# wavtrigger.net
KiCad netlist of a schematic drawn in EAGLE
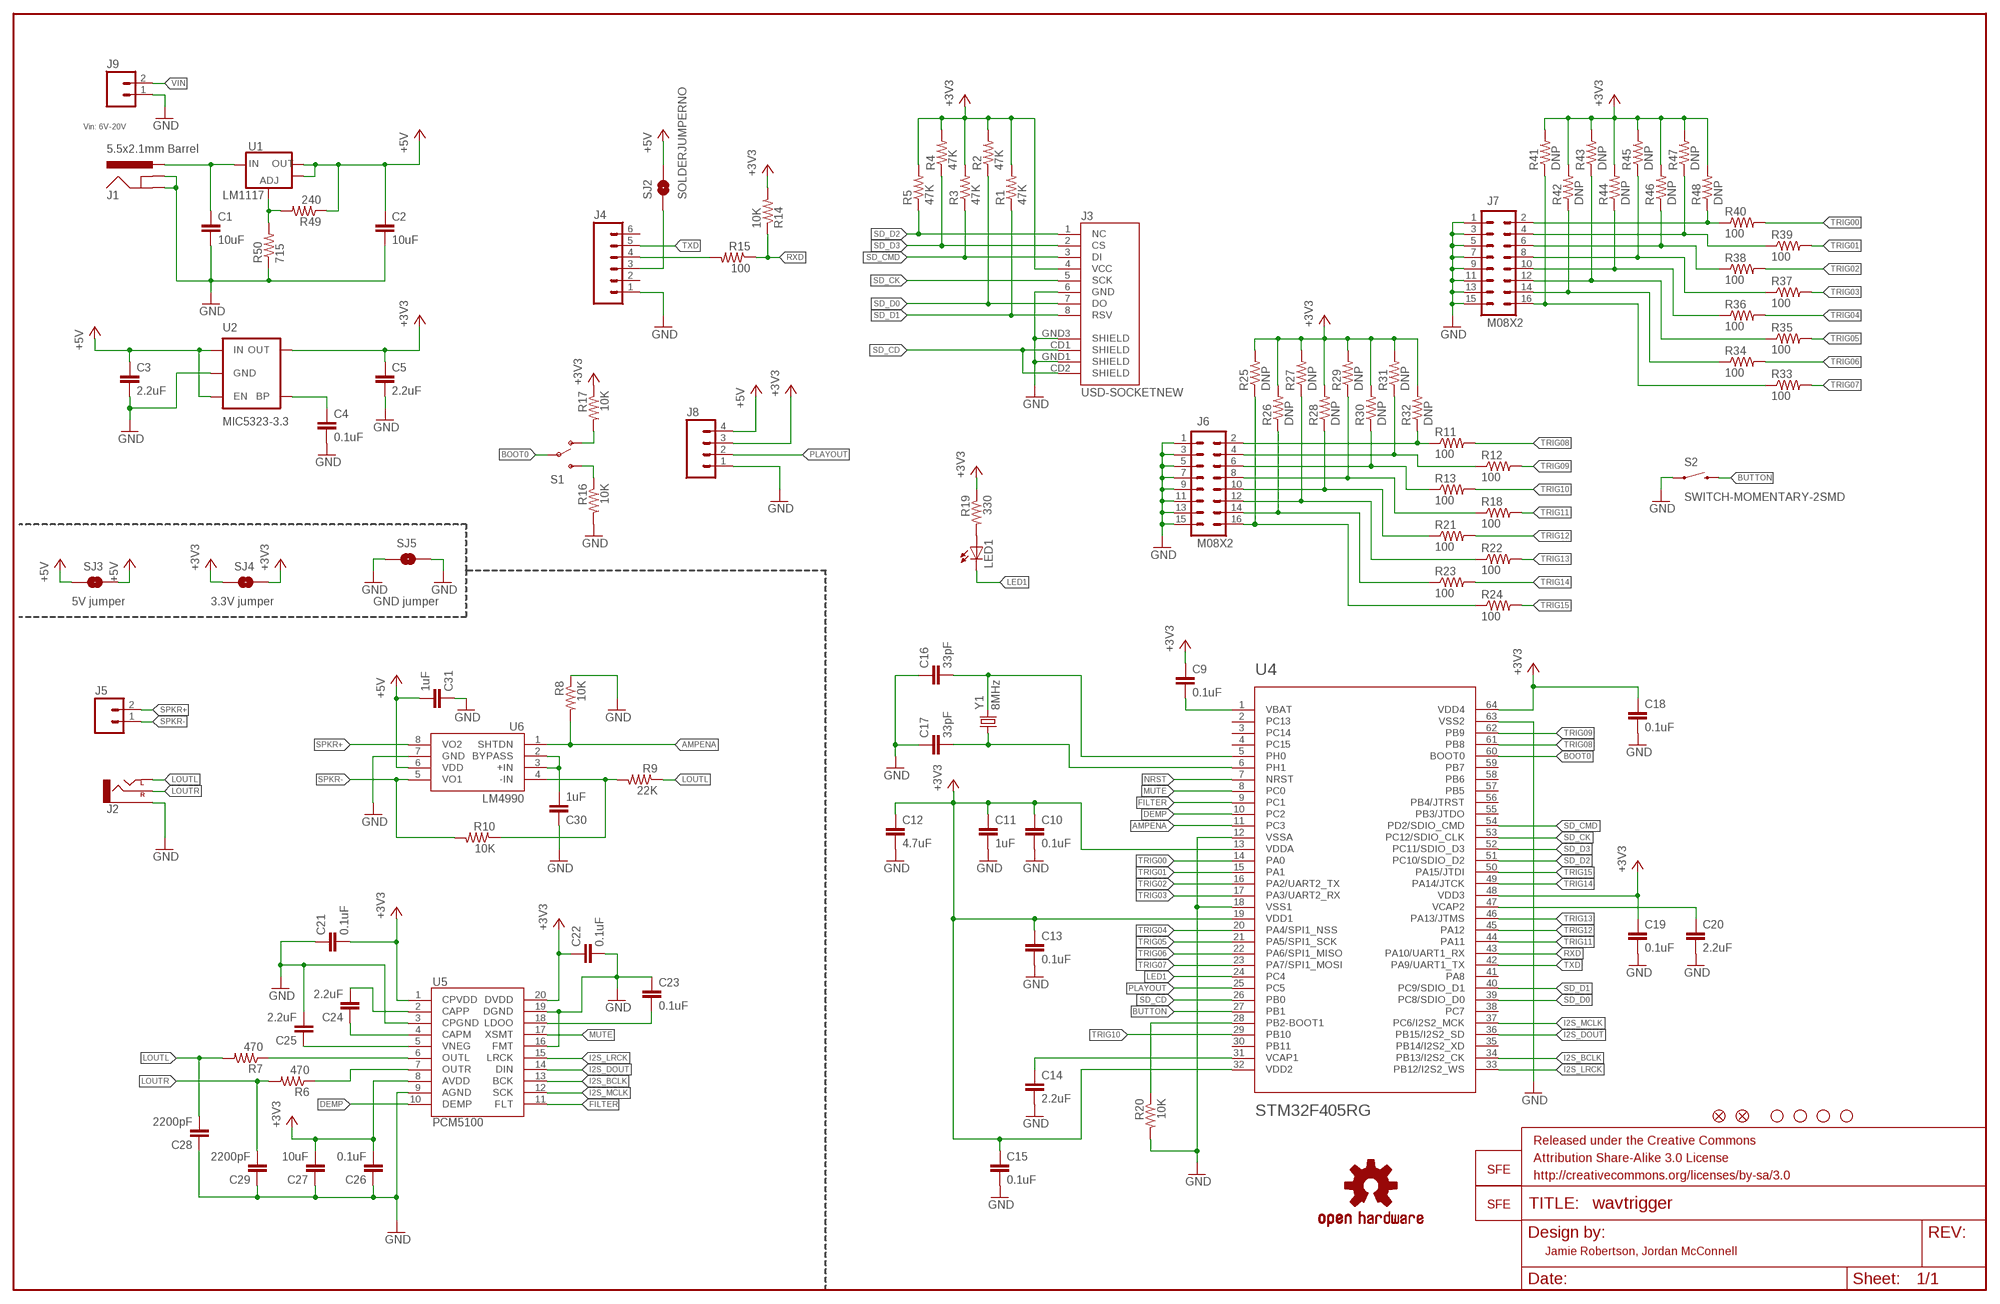
[diagram p0: schematic, sheet 1]

(export (version "E")
  (design (tool "Eeschema 10.0.6"))
  (components
    (comp (ref "C1")
      (value "10uF")
      (footprint "eagle-import:1210")
      (libsource (lib "eagle-import") (part "10UF50V20%(1210)"))
    )
    (comp (ref "C2")
      (value "10uF")
      (footprint "eagle-import:0805")
      (libsource (lib "eagle-import") (part "1UF-25V-10%(0805)"))
    )
    (comp (ref "C3")
      (value "2.2uF")
      (footprint "eagle-import:0805")
      (libsource (lib "eagle-import") (part "1UF-25V-10%(0805)"))
    )
    (comp (ref "C4")
      (value "0.1uF")
      (footprint "eagle-import:0603-CAP")
      (libsource (lib "eagle-import") (part "CAP0603-CAP"))
    )
    (comp (ref "C5")
      (value "2.2uF")
      (footprint "eagle-import:0805")
      (libsource (lib "eagle-import") (part "1UF-25V-10%(0805)"))
    )
    (comp (ref "C9")
      (value "0.1uF")
      (footprint "eagle-import:0603-CAP")
      (libsource (lib "eagle-import") (part "CAP0603-CAP"))
    )
    (comp (ref "C10")
      (value "0.1uF")
      (footprint "eagle-import:0603-CAP")
      (libsource (lib "eagle-import") (part "CAP0603-CAP"))
    )
    (comp (ref "C11")
      (value "1uF")
      (footprint "eagle-import:0603-CAP")
      (libsource (lib "eagle-import") (part "CAP0603-CAP"))
    )
    (comp (ref "C12")
      (value "4.7uF")
      (footprint "eagle-import:0603-CAP")
      (libsource (lib "eagle-import") (part "CAP0603-CAP"))
    )
    (comp (ref "C13")
      (value "0.1uF")
      (footprint "eagle-import:0603-CAP")
      (libsource (lib "eagle-import") (part "CAP0603-CAP"))
    )
    (comp (ref "C14")
      (value "2.2uF")
      (footprint "eagle-import:0603-CAP")
      (libsource (lib "eagle-import") (part "CAP0603-CAP"))
    )
    (comp (ref "C15")
      (value "0.1uF")
      (footprint "eagle-import:0603-CAP")
      (libsource (lib "eagle-import") (part "CAP0603-CAP"))
    )
    (comp (ref "C16")
      (value "33pF")
      (footprint "eagle-import:0603-CAP")
      (libsource (lib "eagle-import") (part "CAP0603-CAP"))
    )
    (comp (ref "C17")
      (value "33pF")
      (footprint "eagle-import:0603-CAP")
      (libsource (lib "eagle-import") (part "CAP0603-CAP"))
    )
    (comp (ref "C18")
      (value "0.1uF")
      (footprint "eagle-import:0603-CAP")
      (libsource (lib "eagle-import") (part "CAP0603-CAP"))
    )
    (comp (ref "C19")
      (value "0.1uF")
      (footprint "eagle-import:0603-CAP")
      (libsource (lib "eagle-import") (part "CAP0603-CAP"))
    )
    (comp (ref "C20")
      (value "2.2uF")
      (footprint "eagle-import:0603-CAP")
      (libsource (lib "eagle-import") (part "CAP0603-CAP"))
    )
    (comp (ref "C21")
      (value "0.1uF")
      (footprint "eagle-import:0603-CAP")
      (libsource (lib "eagle-import") (part "CAP0603-CAP"))
    )
    (comp (ref "C22")
      (value "0.1uF")
      (footprint "eagle-import:0603-CAP")
      (libsource (lib "eagle-import") (part "CAP0603-CAP"))
    )
    (comp (ref "C23")
      (value "0.1uF")
      (footprint "eagle-import:0603-CAP")
      (libsource (lib "eagle-import") (part "CAP0603-CAP"))
    )
    (comp (ref "C24")
      (value "2.2uF")
      (footprint "eagle-import:0603-CAP")
      (libsource (lib "eagle-import") (part "CAP0603-CAP"))
    )
    (comp (ref "C25")
      (value "2.2uF")
      (footprint "eagle-import:0603-CAP")
      (libsource (lib "eagle-import") (part "CAP0603-CAP"))
    )
    (comp (ref "C26")
      (value "0.1uF")
      (footprint "eagle-import:0603-CAP")
      (libsource (lib "eagle-import") (part "CAP0603-CAP"))
    )
    (comp (ref "C27")
      (value "10uF")
      (footprint "eagle-import:0603-CAP")
      (libsource (lib "eagle-import") (part "CAP0603-CAP"))
    )
    (comp (ref "C28")
      (value "2200pF")
      (footprint "eagle-import:0603-CAP")
      (libsource (lib "eagle-import") (part "CAP0603-CAP"))
    )
    (comp (ref "C29")
      (value "2200pF")
      (footprint "eagle-import:0603-CAP")
      (libsource (lib "eagle-import") (part "CAP0603-CAP"))
    )
    (comp (ref "C30")
      (value "1uF")
      (footprint "eagle-import:0603-CAP")
      (libsource (lib "eagle-import") (part "CAP0603-CAP"))
    )
    (comp (ref "C31")
      (value "1uF")
      (footprint "eagle-import:0603-CAP")
      (libsource (lib "eagle-import") (part "CAP0603-CAP"))
    )
    (comp (ref "FID1")
      (value "FIDUCIAL1X2")
      (footprint "eagle-import:FIDUCIAL-1X2")
      (libsource (lib "eagle-import") (part "FIDUCIAL1X2"))
    )
    (comp (ref "FID2")
      (value "FIDUCIAL1X2")
      (footprint "eagle-import:FIDUCIAL-1X2")
      (libsource (lib "eagle-import") (part "FIDUCIAL1X2"))
    )
    (comp (ref "FRAME2")
      (value "FRAME-LEDGER")
      (footprint "eagle-import:CREATIVE_COMMONS")
      (libsource (lib "eagle-import") (part "FRAME-LEDGER"))
    )
    (comp (ref "J1")
      (value "5.5x2.1mm Barrel")
      (footprint "eagle-import:POWER_JACK_SMD")
      (libsource (lib "eagle-import") (part "POWER_JACKSMD"))
    )
    (comp (ref "J2")
      (value "AUDIO-JACKSMD2")
      (footprint "eagle-import:AUDIO-JACK-3.5MM-SMD")
      (libsource (lib "eagle-import") (part "AUDIO-JACKSMD2"))
    )
    (comp (ref "J3")
      (value "USD-SOCKETNEW")
      (footprint "eagle-import:MICRO-SD-SOCKET-PP")
      (libsource (lib "eagle-import") (part "USD-SOCKETNEW"))
    )
    (comp (ref "J4")
      (value "M06SIP")
      (footprint "eagle-import:1X06")
      (libsource (lib "eagle-import") (part "M06SIP"))
    )
    (comp (ref "J5")
      (value "M02PTH")
      (footprint "eagle-import:1X02")
      (libsource (lib "eagle-import") (part "M02PTH"))
    )
    (comp (ref "J6")
      (value "M08X2")
      (footprint "eagle-import:2X8")
      (libsource (lib "eagle-import") (part "M08X2"))
    )
    (comp (ref "J7")
      (value "M08X2")
      (footprint "eagle-import:2X8")
      (libsource (lib "eagle-import") (part "M08X2"))
    )
    (comp (ref "J8")
      (value "M04PTH")
      (footprint "eagle-import:1X04")
      (libsource (lib "eagle-import") (part "M04PTH"))
    )
    (comp (ref "J9")
      (value "M02PTH")
      (footprint "eagle-import:1X02")
      (libsource (lib "eagle-import") (part "M02PTH"))
    )
    (comp (ref "LED1")
      (value "LED0603")
      (footprint "eagle-import:LED-0603")
      (libsource (lib "eagle-import") (part "LED0603"))
    )
    (comp (ref "LOGO1")
      (value "OSHW-LOGOL")
      (footprint "eagle-import:OSHW-LOGO-L")
      (libsource (lib "eagle-import") (part "OSHW-LOGOL"))
    )
    (comp (ref "LOGO2")
      (value "LOGO-SFENEW")
      (footprint "eagle-import:SFE-NEW-WEBLOGO")
      (libsource (lib "eagle-import") (part "LOGO-SFENEW"))
    )
    (comp (ref "LOGO3")
      (value "LOGO-SFESK")
      (footprint "eagle-import:SFE-LOGO-FLAME")
      (libsource (lib "eagle-import") (part "LOGO-SFESK"))
    )
    (comp (ref "R1")
      (value "47K")
      (footprint "eagle-import:0603-RES")
      (libsource (lib "eagle-import") (part "RESISTOR0603-RES"))
    )
    (comp (ref "R2")
      (value "47K")
      (footprint "eagle-import:0603-RES")
      (libsource (lib "eagle-import") (part "RESISTOR0603-RES"))
    )
    (comp (ref "R3")
      (value "47K")
      (footprint "eagle-import:0603-RES")
      (libsource (lib "eagle-import") (part "RESISTOR0603-RES"))
    )
    (comp (ref "R4")
      (value "47K")
      (footprint "eagle-import:0603-RES")
      (libsource (lib "eagle-import") (part "RESISTOR0603-RES"))
    )
    (comp (ref "R5")
      (value "47K")
      (footprint "eagle-import:0603-RES")
      (libsource (lib "eagle-import") (part "RESISTOR0603-RES"))
    )
    (comp (ref "R6")
      (value "470")
      (footprint "eagle-import:0603-RES")
      (libsource (lib "eagle-import") (part "RESISTOR0603-RES"))
    )
    (comp (ref "R7")
      (value "470")
      (footprint "eagle-import:0603-RES")
      (libsource (lib "eagle-import") (part "RESISTOR0603-RES"))
    )
    (comp (ref "R8")
      (value "10K")
      (footprint "eagle-import:0603-RES")
      (libsource (lib "eagle-import") (part "RESISTOR0603-RES"))
    )
    (comp (ref "R9")
      (value "22K")
      (footprint "eagle-import:0603-RES")
      (libsource (lib "eagle-import") (part "RESISTOR0603-RES"))
    )
    (comp (ref "R10")
      (value "10K")
      (footprint "eagle-import:0603-RES")
      (libsource (lib "eagle-import") (part "RESISTOR0603-RES"))
    )
    (comp (ref "R11")
      (value "100")
      (footprint "eagle-import:0603-RES")
      (libsource (lib "eagle-import") (part "RESISTOR0603-RES"))
    )
    (comp (ref "R12")
      (value "100")
      (footprint "eagle-import:0603-RES")
      (libsource (lib "eagle-import") (part "RESISTOR0603-RES"))
    )
    (comp (ref "R13")
      (value "100")
      (footprint "eagle-import:0603-RES")
      (libsource (lib "eagle-import") (part "RESISTOR0603-RES"))
    )
    (comp (ref "R14")
      (value "10K")
      (footprint "eagle-import:0603-RES")
      (libsource (lib "eagle-import") (part "RESISTOR0603-RES"))
    )
    (comp (ref "R15")
      (value "100")
      (footprint "eagle-import:0603-RES")
      (libsource (lib "eagle-import") (part "RESISTOR0603-RES"))
    )
    (comp (ref "R16")
      (value "10K")
      (footprint "eagle-import:0603-RES")
      (libsource (lib "eagle-import") (part "RESISTOR0603-RES"))
    )
    (comp (ref "R17")
      (value "10K")
      (footprint "eagle-import:0603-RES")
      (libsource (lib "eagle-import") (part "RESISTOR0603-RES"))
    )
    (comp (ref "R18")
      (value "100")
      (footprint "eagle-import:0603-RES")
      (libsource (lib "eagle-import") (part "RESISTOR0603-RES"))
    )
    (comp (ref "R19")
      (value "330")
      (footprint "eagle-import:0603-RES")
      (libsource (lib "eagle-import") (part "RESISTOR0603-RES"))
    )
    (comp (ref "R20")
      (value "10K")
      (footprint "eagle-import:0603-RES")
      (libsource (lib "eagle-import") (part "RESISTOR0603-RES"))
    )
    (comp (ref "R21")
      (value "100")
      (footprint "eagle-import:0603-RES")
      (libsource (lib "eagle-import") (part "RESISTOR0603-RES"))
    )
    (comp (ref "R22")
      (value "100")
      (footprint "eagle-import:0603-RES")
      (libsource (lib "eagle-import") (part "RESISTOR0603-RES"))
    )
    (comp (ref "R23")
      (value "100")
      (footprint "eagle-import:0603-RES")
      (libsource (lib "eagle-import") (part "RESISTOR0603-RES"))
    )
    (comp (ref "R24")
      (value "100")
      (footprint "eagle-import:0603-RES")
      (libsource (lib "eagle-import") (part "RESISTOR0603-RES"))
    )
    (comp (ref "R25")
      (value "DNP")
      (footprint "eagle-import:0603-RES")
      (libsource (lib "eagle-import") (part "RESISTOR0603-RES"))
    )
    (comp (ref "R26")
      (value "DNP")
      (footprint "eagle-import:0603-RES")
      (libsource (lib "eagle-import") (part "RESISTOR0603-RES"))
    )
    (comp (ref "R27")
      (value "DNP")
      (footprint "eagle-import:0603-RES")
      (libsource (lib "eagle-import") (part "RESISTOR0603-RES"))
    )
    (comp (ref "R28")
      (value "DNP")
      (footprint "eagle-import:0603-RES")
      (libsource (lib "eagle-import") (part "RESISTOR0603-RES"))
    )
    (comp (ref "R29")
      (value "DNP")
      (footprint "eagle-import:0603-RES")
      (libsource (lib "eagle-import") (part "RESISTOR0603-RES"))
    )
    (comp (ref "R30")
      (value "DNP")
      (footprint "eagle-import:0603-RES")
      (libsource (lib "eagle-import") (part "RESISTOR0603-RES"))
    )
    (comp (ref "R31")
      (value "DNP")
      (footprint "eagle-import:0603-RES")
      (libsource (lib "eagle-import") (part "RESISTOR0603-RES"))
    )
    (comp (ref "R32")
      (value "DNP")
      (footprint "eagle-import:0603-RES")
      (libsource (lib "eagle-import") (part "RESISTOR0603-RES"))
    )
    (comp (ref "R33")
      (value "100")
      (footprint "eagle-import:0603-RES")
      (libsource (lib "eagle-import") (part "RESISTOR0603-RES"))
    )
    (comp (ref "R34")
      (value "100")
      (footprint "eagle-import:0603-RES")
      (libsource (lib "eagle-import") (part "RESISTOR0603-RES"))
    )
    (comp (ref "R35")
      (value "100")
      (footprint "eagle-import:0603-RES")
      (libsource (lib "eagle-import") (part "RESISTOR0603-RES"))
    )
    (comp (ref "R36")
      (value "100")
      (footprint "eagle-import:0603-RES")
      (libsource (lib "eagle-import") (part "RESISTOR0603-RES"))
    )
    (comp (ref "R37")
      (value "100")
      (footprint "eagle-import:0603-RES")
      (libsource (lib "eagle-import") (part "RESISTOR0603-RES"))
    )
    (comp (ref "R38")
      (value "100")
      (footprint "eagle-import:0603-RES")
      (libsource (lib "eagle-import") (part "RESISTOR0603-RES"))
    )
    (comp (ref "R39")
      (value "100")
      (footprint "eagle-import:0603-RES")
      (libsource (lib "eagle-import") (part "RESISTOR0603-RES"))
    )
    (comp (ref "R40")
      (value "100")
      (footprint "eagle-import:0603-RES")
      (libsource (lib "eagle-import") (part "RESISTOR0603-RES"))
    )
    (comp (ref "R41")
      (value "DNP")
      (footprint "eagle-import:0603-RES")
      (libsource (lib "eagle-import") (part "RESISTOR0603-RES"))
    )
    (comp (ref "R42")
      (value "DNP")
      (footprint "eagle-import:0603-RES")
      (libsource (lib "eagle-import") (part "RESISTOR0603-RES"))
    )
    (comp (ref "R43")
      (value "DNP")
      (footprint "eagle-import:0603-RES")
      (libsource (lib "eagle-import") (part "RESISTOR0603-RES"))
    )
    (comp (ref "R44")
      (value "DNP")
      (footprint "eagle-import:0603-RES")
      (libsource (lib "eagle-import") (part "RESISTOR0603-RES"))
    )
    (comp (ref "R45")
      (value "DNP")
      (footprint "eagle-import:0603-RES")
      (libsource (lib "eagle-import") (part "RESISTOR0603-RES"))
    )
    (comp (ref "R46")
      (value "DNP")
      (footprint "eagle-import:0603-RES")
      (libsource (lib "eagle-import") (part "RESISTOR0603-RES"))
    )
    (comp (ref "R47")
      (value "DNP")
      (footprint "eagle-import:0603-RES")
      (libsource (lib "eagle-import") (part "RESISTOR0603-RES"))
    )
    (comp (ref "R48")
      (value "DNP")
      (footprint "eagle-import:0603-RES")
      (libsource (lib "eagle-import") (part "RESISTOR0603-RES"))
    )
    (comp (ref "R49")
      (value "240")
      (footprint "eagle-import:0603-RES")
      (libsource (lib "eagle-import") (part "240OHM1/10W1%(0603)"))
    )
    (comp (ref "R50")
      (value "715")
      (footprint "eagle-import:0603-RES")
      (libsource (lib "eagle-import") (part "RESISTOR0603"))
    )
    (comp (ref "S1")
      (value "SWITCH-SPDT-SMD-A")
      (footprint "eagle-import:SWITCH-SPST-SMD-A")
      (libsource (lib "eagle-import") (part "SWITCH-SPDT-SMD-A"))
    )
    (comp (ref "S2")
      (value "SWITCH-MOMENTARY-2SMD")
      (footprint "eagle-import:TACTILE_SWITCH_SMD")
      (libsource (lib "eagle-import") (part "SWITCH-MOMENTARY-2SMD"))
    )
    (comp (ref "SJ2")
      (value "SOLDERJUMPERNO")
      (footprint "eagle-import:SJ_2S-NO")
      (libsource (lib "eagle-import") (part "SOLDERJUMPERNO"))
    )
    (comp (ref "SJ3")
      (value "SOLDERJUMPERTRACE")
      (footprint "eagle-import:SJ_2S-TRACE")
      (libsource (lib "eagle-import") (part "SOLDERJUMPERTRACE"))
    )
    (comp (ref "SJ4")
      (value "SOLDERJUMPERTRACE")
      (footprint "eagle-import:SJ_2S-TRACE")
      (libsource (lib "eagle-import") (part "SOLDERJUMPERTRACE"))
    )
    (comp (ref "SJ5")
      (value "SOLDERJUMPERTRACE")
      (footprint "eagle-import:SJ_2S-TRACE")
      (libsource (lib "eagle-import") (part "SOLDERJUMPERTRACE"))
    )
    (comp (ref "STANDOFF1")
      (value "STAND-OFF")
      (footprint "eagle-import:STAND-OFF")
      (libsource (lib "eagle-import") (part "STAND-OFF"))
    )
    (comp (ref "STANDOFF2")
      (value "STAND-OFF")
      (footprint "eagle-import:STAND-OFF")
      (libsource (lib "eagle-import") (part "STAND-OFF"))
    )
    (comp (ref "STANDOFF3")
      (value "STAND-OFF")
      (footprint "eagle-import:STAND-OFF")
      (libsource (lib "eagle-import") (part "STAND-OFF"))
    )
    (comp (ref "STANDOFF4")
      (value "STAND-OFF")
      (footprint "eagle-import:STAND-OFF")
      (libsource (lib "eagle-import") (part "STAND-OFF"))
    )
    (comp (ref "U1")
      (value "V_REG_LM1117SOT223")
      (footprint "eagle-import:SOT223")
      (libsource (lib "eagle-import") (part "V_REG_LM1117SOT223"))
    )
    (comp (ref "U2")
      (value "MIC5323-3.3")
      (footprint "eagle-import:SOT23-5")
      (libsource (lib "eagle-import") (part "MIC52053.3V"))
    )
    (comp (ref "U4")
      (value "STM32F405RG")
      (footprint "eagle-import:TQFP64")
      (libsource (lib "eagle-import") (part "STM32F405RG"))
    )
    (comp (ref "U5")
      (value "PCM5100")
      (footprint "eagle-import:PW_R-PDSO-G20")
      (libsource (lib "eagle-import") (part "PCM5100"))
    )
    (comp (ref "U6")
      (value "LM4990")
      (footprint "eagle-import:S-PDSO-G08")
      (libsource (lib "eagle-import") (part "LM4990"))
    )
    (comp (ref "Y1")
      (value "8MHz")
      (footprint "eagle-import:HC49UP")
      (libsource (lib "eagle-import") (part "CRYSTALSMD"))
    )
  )
  (nets
    (net (code "1") (name "+3V3") (class "Default")
      (node (ref "C10") (pin "1") (pinfunction "1_1") (pintype "passive"))
      (node (ref "C11") (pin "1") (pinfunction "1_1") (pintype "passive"))
      (node (ref "C12") (pin "1") (pinfunction "1_1") (pintype "passive"))
      (node (ref "C13") (pin "1") (pinfunction "1_1") (pintype "passive"))
      (node (ref "C15") (pin "1") (pinfunction "1_1") (pintype "passive"))
      (node (ref "C18") (pin "1") (pinfunction "1_1") (pintype "passive"))
      (node (ref "C19") (pin "1") (pinfunction "1_1") (pintype "passive"))
      (node (ref "C21") (pin "2") (pinfunction "2_2") (pintype "passive"))
      (node (ref "C22") (pin "1") (pinfunction "1_1") (pintype "passive"))
      (node (ref "C26") (pin "2") (pinfunction "2_2") (pintype "passive"))
      (node (ref "C27") (pin "2") (pinfunction "2_2") (pintype "passive"))
      (node (ref "C5") (pin "1") (pinfunction "1_1") (pintype "passive"))
      (node (ref "C9") (pin "1") (pinfunction "1_1") (pintype "passive"))
      (node (ref "J3") (pin "4") (pinfunction "VCC_4") (pintype "bidirectional"))
      (node (ref "J8") (pin "3") (pinfunction "3_3") (pintype "passive"))
      (node (ref "R1") (pin "2") (pinfunction "2_2") (pintype "passive"))
      (node (ref "R14") (pin "2") (pinfunction "2_2") (pintype "passive"))
      (node (ref "R17") (pin "1") (pinfunction "1_1") (pintype "passive"))
      (node (ref "R19") (pin "1") (pinfunction "1_1") (pintype "passive"))
      (node (ref "R2") (pin "2") (pinfunction "2_2") (pintype "passive"))
      (node (ref "R25") (pin "2") (pinfunction "2_2") (pintype "passive"))
      (node (ref "R26") (pin "2") (pinfunction "2_2") (pintype "passive"))
      (node (ref "R27") (pin "2") (pinfunction "2_2") (pintype "passive"))
      (node (ref "R28") (pin "2") (pinfunction "2_2") (pintype "passive"))
      (node (ref "R29") (pin "2") (pinfunction "2_2") (pintype "passive"))
      (node (ref "R3") (pin "2") (pinfunction "2_2") (pintype "passive"))
      (node (ref "R30") (pin "2") (pinfunction "2_2") (pintype "passive"))
      (node (ref "R31") (pin "2") (pinfunction "2_2") (pintype "passive"))
      (node (ref "R32") (pin "2") (pinfunction "2_2") (pintype "passive"))
      (node (ref "R4") (pin "2") (pinfunction "2_2") (pintype "passive"))
      (node (ref "R41") (pin "2") (pinfunction "2_2") (pintype "passive"))
      (node (ref "R42") (pin "2") (pinfunction "2_2") (pintype "passive"))
      (node (ref "R43") (pin "2") (pinfunction "2_2") (pintype "passive"))
      (node (ref "R44") (pin "2") (pinfunction "2_2") (pintype "passive"))
      (node (ref "R45") (pin "2") (pinfunction "2_2") (pintype "passive"))
      (node (ref "R46") (pin "2") (pinfunction "2_2") (pintype "passive"))
      (node (ref "R47") (pin "2") (pinfunction "2_2") (pintype "passive"))
      (node (ref "R48") (pin "2") (pinfunction "2_2") (pintype "passive"))
      (node (ref "R5") (pin "2") (pinfunction "2_2") (pintype "passive"))
      (node (ref "SJ4") (pin "1") (pinfunction "1_1") (pintype "passive"))
      (node (ref "SJ4") (pin "2") (pinfunction "2_2") (pintype "passive"))
      (node (ref "U2") (pin "5") (pinfunction "OUT_5") (pintype "passive"))
      (node (ref "U4") (pin "13") (pinfunction "VDDA_13") (pintype "bidirectional"))
      (node (ref "U4") (pin "19") (pinfunction "VDD1_19") (pintype "bidirectional"))
      (node (ref "U4") (pin "32") (pinfunction "VDD2_32") (pintype "bidirectional"))
      (node (ref "U4") (pin "48") (pinfunction "VDD3_48") (pintype "bidirectional"))
      (node (ref "U4") (pin "64") (pinfunction "VDD4_64") (pintype "bidirectional"))
      (node (ref "U5") (pin "1") (pinfunction "CPVDD_1") (pintype "bidirectional"))
      (node (ref "U5") (pin "20") (pinfunction "DVDD_20") (pintype "bidirectional"))
      (node (ref "U5") (pin "8") (pinfunction "AVDD_8") (pintype "bidirectional"))
    )
    (net (code "2") (name "+5V") (class "Default")
      (node (ref "C2") (pin "1") (pinfunction "1_1") (pintype "passive"))
      (node (ref "C3") (pin "1") (pinfunction "1_1") (pintype "passive"))
      (node (ref "C31") (pin "2") (pinfunction "2_2") (pintype "passive"))
      (node (ref "J8") (pin "4") (pinfunction "4_4") (pintype "passive"))
      (node (ref "R49") (pin "1") (pinfunction "1_1") (pintype "passive"))
      (node (ref "SJ2") (pin "2") (pinfunction "2_2") (pintype "passive"))
      (node (ref "SJ3") (pin "1") (pinfunction "1_1") (pintype "passive"))
      (node (ref "SJ3") (pin "2") (pinfunction "2_2") (pintype "passive"))
      (node (ref "U1") (pin "2") (pinfunction "OUT_2") (pintype "output"))
      (node (ref "U1") (pin "4") (pinfunction "OUT_4") (pintype "output"))
      (node (ref "U2") (pin "1") (pinfunction "IN_1") (pintype "input"))
      (node (ref "U2") (pin "3") (pinfunction "EN_3") (pintype "input"))
      (node (ref "U6") (pin "6") (pinfunction "VDD_6") (pintype "bidirectional"))
    )
    (net (code "3") (name "AMPENA") (class "Default")
      (node (ref "R8") (pin "2") (pinfunction "2_2") (pintype "passive"))
      (node (ref "U4") (pin "11") (pinfunction "PC3_11") (pintype "bidirectional"))
      (node (ref "U6") (pin "1") (pinfunction "SHTDN_1") (pintype "bidirectional"))
    )
    (net (code "4") (name "BOOT0") (class "Default")
      (node (ref "S1") (pin "2") (pinfunction "P_2") (pintype "passive"))
      (node (ref "U4") (pin "60") (pinfunction "BOOT0_60") (pintype "bidirectional"))
    )
    (net (code "5") (name "BUTTON") (class "Default")
      (node (ref "S2") (pin "3") (pinfunction "2_3") (pintype "passive"))
      (node (ref "U4") (pin "27") (pinfunction "PB1_27") (pintype "bidirectional"))
    )
    (net (code "6") (name "DEMP") (class "Default")
      (node (ref "U4") (pin "10") (pinfunction "PC2_10") (pintype "bidirectional"))
      (node (ref "U5") (pin "10") (pinfunction "DEMP_10") (pintype "bidirectional"))
    )
    (net (code "7") (name "FILTER") (class "Default")
      (node (ref "U4") (pin "9") (pinfunction "PC1_9") (pintype "bidirectional"))
      (node (ref "U5") (pin "11") (pinfunction "FLT_11") (pintype "bidirectional"))
    )
    (net (code "8") (name "GND") (class "Default")
      (node (ref "C1") (pin "2") (pinfunction "2_2") (pintype "passive"))
      (node (ref "C10") (pin "2") (pinfunction "2_2") (pintype "passive"))
      (node (ref "C11") (pin "2") (pinfunction "2_2") (pintype "passive"))
      (node (ref "C12") (pin "2") (pinfunction "2_2") (pintype "passive"))
      (node (ref "C13") (pin "2") (pinfunction "2_2") (pintype "passive"))
      (node (ref "C14") (pin "2") (pinfunction "2_2") (pintype "passive"))
      (node (ref "C15") (pin "2") (pinfunction "2_2") (pintype "passive"))
      (node (ref "C16") (pin "1") (pinfunction "1_1") (pintype "passive"))
      (node (ref "C17") (pin "1") (pinfunction "1_1") (pintype "passive"))
      (node (ref "C18") (pin "2") (pinfunction "2_2") (pintype "passive"))
      (node (ref "C19") (pin "2") (pinfunction "2_2") (pintype "passive"))
      (node (ref "C2") (pin "2") (pinfunction "2_2") (pintype "passive"))
      (node (ref "C20") (pin "2") (pinfunction "2_2") (pintype "passive"))
      (node (ref "C21") (pin "1") (pinfunction "1_1") (pintype "passive"))
      (node (ref "C22") (pin "2") (pinfunction "2_2") (pintype "passive"))
      (node (ref "C23") (pin "1") (pinfunction "1_1") (pintype "passive"))
      (node (ref "C25") (pin "2") (pinfunction "2_2") (pintype "passive"))
      (node (ref "C26") (pin "1") (pinfunction "1_1") (pintype "passive"))
      (node (ref "C27") (pin "1") (pinfunction "1_1") (pintype "passive"))
      (node (ref "C28") (pin "1") (pinfunction "1_1") (pintype "passive"))
      (node (ref "C29") (pin "1") (pinfunction "1_1") (pintype "passive"))
      (node (ref "C3") (pin "2") (pinfunction "2_2") (pintype "passive"))
      (node (ref "C30") (pin "1") (pinfunction "1_1") (pintype "passive"))
      (node (ref "C31") (pin "1") (pinfunction "1_1") (pintype "passive"))
      (node (ref "C4") (pin "2") (pinfunction "2_2") (pintype "passive"))
      (node (ref "C5") (pin "2") (pinfunction "2_2") (pintype "passive"))
      (node (ref "J1") (pin "GND") (pinfunction "GNDBREAK_GND") (pintype "bidirectional"))
      (node (ref "J1") (pin "P$4") (pinfunction "GND_P$4") (pintype "bidirectional"))
      (node (ref "J2") (pin "SLEEVE") (pinfunction "SLEEVE_SLEEVE") (pintype "bidirectional"))
      (node (ref "J3") (pin "6") (pinfunction "GND_6") (pintype "bidirectional"))
      (node (ref "J3") (pin "GND1") (pinfunction "SHIELD_GND1") (pintype "bidirectional"))
      (node (ref "J3") (pin "GND3") (pinfunction "SHIELD_GND3") (pintype "bidirectional"))
      (node (ref "J4") (pin "1") (pinfunction "1_1") (pintype "passive"))
      (node (ref "J6") (pin "1") (pinfunction "1_1") (pintype "passive"))
      (node (ref "J6") (pin "11") (pinfunction "11_11") (pintype "passive"))
      (node (ref "J6") (pin "13") (pinfunction "13_13") (pintype "passive"))
      (node (ref "J6") (pin "15") (pinfunction "15_15") (pintype "passive"))
      (node (ref "J6") (pin "3") (pinfunction "3_3") (pintype "passive"))
      (node (ref "J6") (pin "5") (pinfunction "5_5") (pintype "passive"))
      (node (ref "J6") (pin "7") (pinfunction "7_7") (pintype "passive"))
      (node (ref "J6") (pin "9") (pinfunction "9_9") (pintype "passive"))
      (node (ref "J7") (pin "1") (pinfunction "1_1") (pintype "passive"))
      (node (ref "J7") (pin "11") (pinfunction "11_11") (pintype "passive"))
      (node (ref "J7") (pin "13") (pinfunction "13_13") (pintype "passive"))
      (node (ref "J7") (pin "15") (pinfunction "15_15") (pintype "passive"))
      (node (ref "J7") (pin "3") (pinfunction "3_3") (pintype "passive"))
      (node (ref "J7") (pin "5") (pinfunction "5_5") (pintype "passive"))
      (node (ref "J7") (pin "7") (pinfunction "7_7") (pintype "passive"))
      (node (ref "J7") (pin "9") (pinfunction "9_9") (pintype "passive"))
      (node (ref "J8") (pin "1") (pinfunction "1_1") (pintype "passive"))
      (node (ref "J9") (pin "1") (pinfunction "1_1") (pintype "passive"))
      (node (ref "R16") (pin "2") (pinfunction "2_2") (pintype "passive"))
      (node (ref "R20") (pin "2") (pinfunction "2_2") (pintype "passive"))
      (node (ref "R50") (pin "1") (pinfunction "1_1") (pintype "passive"))
      (node (ref "R8") (pin "1") (pinfunction "1_1") (pintype "passive"))
      (node (ref "S2") (pin "1") (pinfunction "1_1") (pintype "passive"))
      (node (ref "SJ5") (pin "1") (pinfunction "1_1") (pintype "passive"))
      (node (ref "SJ5") (pin "2") (pinfunction "2_2") (pintype "passive"))
      (node (ref "U2") (pin "2") (pinfunction "GND_2") (pintype "input"))
      (node (ref "U4") (pin "12") (pinfunction "VSSA_12") (pintype "bidirectional"))
      (node (ref "U4") (pin "18") (pinfunction "VSS1_18") (pintype "bidirectional"))
      (node (ref "U4") (pin "63") (pinfunction "VSS2_63") (pintype "bidirectional"))
      (node (ref "U5") (pin "16") (pinfunction "FMT_16") (pintype "bidirectional"))
      (node (ref "U5") (pin "19") (pinfunction "DGND_19") (pintype "bidirectional"))
      (node (ref "U5") (pin "3") (pinfunction "CPGND_3") (pintype "bidirectional"))
      (node (ref "U5") (pin "9") (pinfunction "AGND_9") (pintype "bidirectional"))
      (node (ref "U6") (pin "7") (pinfunction "GND_7") (pintype "bidirectional"))
    )
    (net (code "9") (name "I2S_BCLK") (class "Default")
      (node (ref "U4") (pin "34") (pinfunction "PB13/I2S2_CK_34") (pintype "bidirectional"))
      (node (ref "U5") (pin "13") (pinfunction "BCK_13") (pintype "bidirectional"))
    )
    (net (code "10") (name "I2S_DOUT") (class "Default")
      (node (ref "U4") (pin "36") (pinfunction "PB15/I2S2_SD_36") (pintype "bidirectional"))
      (node (ref "U5") (pin "14") (pinfunction "DIN_14") (pintype "bidirectional"))
    )
    (net (code "11") (name "I2S_LRCK") (class "Default")
      (node (ref "U4") (pin "33") (pinfunction "PB12/I2S2_WS_33") (pintype "bidirectional"))
      (node (ref "U5") (pin "15") (pinfunction "LRCK_15") (pintype "bidirectional"))
    )
    (net (code "12") (name "I2S_MCLK") (class "Default")
      (node (ref "U4") (pin "37") (pinfunction "PC6/I2S2_MCK_37") (pintype "bidirectional"))
      (node (ref "U5") (pin "12") (pinfunction "SCK_12") (pintype "bidirectional"))
    )
    (net (code "13") (name "LED1") (class "Default")
      (node (ref "LED1") (pin "C") (pinfunction "C_C") (pintype "passive"))
      (node (ref "U4") (pin "24") (pinfunction "PC4_24") (pintype "bidirectional"))
    )
    (net (code "14") (name "LOUTL") (class "Default")
      (node (ref "C28") (pin "2") (pinfunction "2_2") (pintype "passive"))
      (node (ref "J2") (pin "TIP") (pinfunction "LEFT_TIP") (pintype "bidirectional"))
      (node (ref "R7") (pin "2") (pinfunction "2_2") (pintype "passive"))
      (node (ref "R9") (pin "1") (pinfunction "1_1") (pintype "passive"))
    )
    (net (code "15") (name "LOUTR") (class "Default")
      (node (ref "C29") (pin "2") (pinfunction "2_2") (pintype "passive"))
      (node (ref "J2") (pin "RING") (pinfunction "RIGHT_RING") (pintype "bidirectional"))
      (node (ref "R6") (pin "2") (pinfunction "2_2") (pintype "passive"))
    )
    (net (code "16") (name "MUTE") (class "Default")
      (node (ref "U4") (pin "8") (pinfunction "PC0_8") (pintype "bidirectional"))
      (node (ref "U5") (pin "17") (pinfunction "XSMT_17") (pintype "bidirectional"))
    )
    (net (code "17") (name "NRST") (class "Default")
      (node (ref "U4") (pin "7") (pinfunction "NRST_7") (pintype "bidirectional"))
    )
    (net (code "18") (name "Net-(J4-Pad3)") (class "Default")
      (node (ref "J4") (pin "3") (pinfunction "3_3") (pintype "passive"))
      (node (ref "SJ2") (pin "1") (pinfunction "1_1") (pintype "passive"))
    )
    (net (code "19") (name "Net-(J4-Pad4)") (class "Default")
      (node (ref "J4") (pin "4") (pinfunction "4_4") (pintype "passive"))
      (node (ref "R15") (pin "2") (pinfunction "2_2") (pintype "passive"))
    )
    (net (code "20") (name "Net-(J6-Pad2)") (class "Default")
      (node (ref "J6") (pin "2") (pinfunction "2_2") (pintype "passive"))
      (node (ref "R11") (pin "1") (pinfunction "1_1") (pintype "passive"))
      (node (ref "R32") (pin "1") (pinfunction "1_1") (pintype "passive"))
    )
    (net (code "21") (name "Net-(J6-Pad4)") (class "Default")
      (node (ref "J6") (pin "4") (pinfunction "4_4") (pintype "passive"))
      (node (ref "R12") (pin "1") (pinfunction "1_1") (pintype "passive"))
      (node (ref "R31") (pin "1") (pinfunction "1_1") (pintype "passive"))
    )
    (net (code "22") (name "Net-(J6-Pad6)") (class "Default")
      (node (ref "J6") (pin "6") (pinfunction "6_6") (pintype "passive"))
      (node (ref "R13") (pin "1") (pinfunction "1_1") (pintype "passive"))
      (node (ref "R30") (pin "1") (pinfunction "1_1") (pintype "passive"))
    )
    (net (code "23") (name "Net-(J6-Pad8)") (class "Default")
      (node (ref "J6") (pin "8") (pinfunction "8_8") (pintype "passive"))
      (node (ref "R18") (pin "1") (pinfunction "1_1") (pintype "passive"))
      (node (ref "R29") (pin "1") (pinfunction "1_1") (pintype "passive"))
    )
    (net (code "24") (name "Net-(J6-Pad10)") (class "Default")
      (node (ref "J6") (pin "10") (pinfunction "10_10") (pintype "passive"))
      (node (ref "R21") (pin "1") (pinfunction "1_1") (pintype "passive"))
      (node (ref "R28") (pin "1") (pinfunction "1_1") (pintype "passive"))
    )
    (net (code "25") (name "Net-(J6-Pad12)") (class "Default")
      (node (ref "J6") (pin "12") (pinfunction "12_12") (pintype "passive"))
      (node (ref "R22") (pin "1") (pinfunction "1_1") (pintype "passive"))
      (node (ref "R27") (pin "1") (pinfunction "1_1") (pintype "passive"))
    )
    (net (code "26") (name "Net-(J6-Pad14)") (class "Default")
      (node (ref "J6") (pin "14") (pinfunction "14_14") (pintype "passive"))
      (node (ref "R23") (pin "1") (pinfunction "1_1") (pintype "passive"))
      (node (ref "R26") (pin "1") (pinfunction "1_1") (pintype "passive"))
    )
    (net (code "27") (name "Net-(J6-Pad16)") (class "Default")
      (node (ref "J6") (pin "16") (pinfunction "16_16") (pintype "passive"))
      (node (ref "R24") (pin "1") (pinfunction "1_1") (pintype "passive"))
      (node (ref "R25") (pin "1") (pinfunction "1_1") (pintype "passive"))
    )
    (net (code "28") (name "Net-(J7-Pad2)") (class "Default")
      (node (ref "J7") (pin "2") (pinfunction "2_2") (pintype "passive"))
      (node (ref "R40") (pin "1") (pinfunction "1_1") (pintype "passive"))
      (node (ref "R48") (pin "1") (pinfunction "1_1") (pintype "passive"))
    )
    (net (code "29") (name "Net-(J7-Pad4)") (class "Default")
      (node (ref "J7") (pin "4") (pinfunction "4_4") (pintype "passive"))
      (node (ref "R39") (pin "1") (pinfunction "1_1") (pintype "passive"))
      (node (ref "R47") (pin "1") (pinfunction "1_1") (pintype "passive"))
    )
    (net (code "30") (name "Net-(J7-Pad6)") (class "Default")
      (node (ref "J7") (pin "6") (pinfunction "6_6") (pintype "passive"))
      (node (ref "R38") (pin "1") (pinfunction "1_1") (pintype "passive"))
      (node (ref "R46") (pin "1") (pinfunction "1_1") (pintype "passive"))
    )
    (net (code "31") (name "Net-(J7-Pad8)") (class "Default")
      (node (ref "J7") (pin "8") (pinfunction "8_8") (pintype "passive"))
      (node (ref "R37") (pin "1") (pinfunction "1_1") (pintype "passive"))
      (node (ref "R45") (pin "1") (pinfunction "1_1") (pintype "passive"))
    )
    (net (code "32") (name "Net-(J7-Pad10)") (class "Default")
      (node (ref "J7") (pin "10") (pinfunction "10_10") (pintype "passive"))
      (node (ref "R36") (pin "1") (pinfunction "1_1") (pintype "passive"))
      (node (ref "R44") (pin "1") (pinfunction "1_1") (pintype "passive"))
    )
    (net (code "33") (name "Net-(J7-Pad12)") (class "Default")
      (node (ref "J7") (pin "12") (pinfunction "12_12") (pintype "passive"))
      (node (ref "R35") (pin "1") (pinfunction "1_1") (pintype "passive"))
      (node (ref "R43") (pin "1") (pinfunction "1_1") (pintype "passive"))
    )
    (net (code "34") (name "Net-(J7-Pad14)") (class "Default")
      (node (ref "J7") (pin "14") (pinfunction "14_14") (pintype "passive"))
      (node (ref "R34") (pin "1") (pinfunction "1_1") (pintype "passive"))
      (node (ref "R42") (pin "1") (pinfunction "1_1") (pintype "passive"))
    )
    (net (code "35") (name "Net-(J7-Pad16)") (class "Default")
      (node (ref "J7") (pin "16") (pinfunction "16_16") (pintype "passive"))
      (node (ref "R33") (pin "1") (pinfunction "1_1") (pintype "passive"))
      (node (ref "R41") (pin "1") (pinfunction "1_1") (pintype "passive"))
    )
    (net (code "36") (name "Net-(LED1-PadA)") (class "Default")
      (node (ref "LED1") (pin "A") (pinfunction "A_A") (pintype "passive"))
      (node (ref "R19") (pin "2") (pinfunction "2_2") (pintype "passive"))
    )
    (net (code "37") (name "Net-(S1-O)") (class "Default")
      (node (ref "R17") (pin "2") (pinfunction "2_2") (pintype "passive"))
      (node (ref "S1") (pin "1") (pinfunction "O_1") (pintype "passive"))
    )
    (net (code "38") (name "Net-(S1-S)") (class "Default")
      (node (ref "R16") (pin "1") (pinfunction "1_1") (pintype "passive"))
      (node (ref "S1") (pin "3") (pinfunction "S_3") (pintype "passive"))
    )
    (net (code "39") (name "Net-(U1-ADJ)") (class "Default")
      (node (ref "R49") (pin "2") (pinfunction "2_2") (pintype "passive"))
      (node (ref "R50") (pin "2") (pinfunction "2_2") (pintype "passive"))
      (node (ref "U1") (pin "1") (pinfunction "ADJ_1") (pintype "input"))
    )
    (net (code "40") (name "Net-(U2-BP)") (class "Default")
      (node (ref "C4") (pin "1") (pinfunction "1_1") (pintype "passive"))
      (node (ref "U2") (pin "4") (pinfunction "BP_4") (pintype "input"))
    )
    (net (code "41") (name "Net-(U4-PB2-BOOT1)") (class "Default")
      (node (ref "R20") (pin "1") (pinfunction "1_1") (pintype "passive"))
      (node (ref "U4") (pin "28") (pinfunction "PB2-BOOT1_28") (pintype "bidirectional"))
    )
    (net (code "42") (name "Net-(U4-PH0)") (class "Default")
      (node (ref "C16") (pin "2") (pinfunction "2_2") (pintype "passive"))
      (node (ref "U4") (pin "5") (pinfunction "PH0_5") (pintype "bidirectional"))
      (node (ref "Y1") (pin "2") (pinfunction "2_2") (pintype "passive"))
    )
    (net (code "43") (name "Net-(U4-PH1)") (class "Default")
      (node (ref "C17") (pin "2") (pinfunction "2_2") (pintype "passive"))
      (node (ref "U4") (pin "6") (pinfunction "PH1_6") (pintype "bidirectional"))
      (node (ref "Y1") (pin "1") (pinfunction "1_1") (pintype "passive"))
    )
    (net (code "44") (name "Net-(U4-VBAT)") (class "Default")
      (node (ref "C9") (pin "2") (pinfunction "2_2") (pintype "passive"))
      (node (ref "U4") (pin "1") (pinfunction "VBAT_1") (pintype "bidirectional"))
    )
    (net (code "45") (name "Net-(U4-VCAP1)") (class "Default")
      (node (ref "C14") (pin "1") (pinfunction "1_1") (pintype "passive"))
      (node (ref "U4") (pin "31") (pinfunction "VCAP1_31") (pintype "bidirectional"))
    )
    (net (code "46") (name "Net-(U4-VCAP2)") (class "Default")
      (node (ref "C20") (pin "1") (pinfunction "1_1") (pintype "passive"))
      (node (ref "U4") (pin "47") (pinfunction "VCAP2_47") (pintype "bidirectional"))
    )
    (net (code "47") (name "Net-(U5-CAPM)") (class "Default")
      (node (ref "C24") (pin "1") (pinfunction "1_1") (pintype "passive"))
      (node (ref "U5") (pin "4") (pinfunction "CAPM_4") (pintype "bidirectional"))
    )
    (net (code "48") (name "Net-(U5-CAPP)") (class "Default")
      (node (ref "C24") (pin "2") (pinfunction "2_2") (pintype "passive"))
      (node (ref "U5") (pin "2") (pinfunction "CAPP_2") (pintype "bidirectional"))
    )
    (net (code "49") (name "Net-(U5-LDOO)") (class "Default")
      (node (ref "C23") (pin "2") (pinfunction "2_2") (pintype "passive"))
      (node (ref "U5") (pin "18") (pinfunction "LDOO_18") (pintype "bidirectional"))
    )
    (net (code "50") (name "Net-(U5-OUTL)") (class "Default")
      (node (ref "R7") (pin "1") (pinfunction "1_1") (pintype "passive"))
      (node (ref "U5") (pin "6") (pinfunction "OUTL_6") (pintype "bidirectional"))
    )
    (net (code "51") (name "Net-(U5-OUTR)") (class "Default")
      (node (ref "R6") (pin "1") (pinfunction "1_1") (pintype "passive"))
      (node (ref "U5") (pin "7") (pinfunction "OUTR_7") (pintype "bidirectional"))
    )
    (net (code "52") (name "Net-(U5-VNEG)") (class "Default")
      (node (ref "C25") (pin "1") (pinfunction "1_1") (pintype "passive"))
      (node (ref "U5") (pin "5") (pinfunction "VNEG_5") (pintype "bidirectional"))
    )
    (net (code "53") (name "Net-(U6-+IN)") (class "Default")
      (node (ref "C30") (pin "2") (pinfunction "2_2") (pintype "passive"))
      (node (ref "U6") (pin "2") (pinfunction "BYPASS_2") (pintype "bidirectional"))
      (node (ref "U6") (pin "3") (pinfunction "+IN_3") (pintype "bidirectional"))
    )
    (net (code "54") (name "Net-(U6--IN)") (class "Default")
      (node (ref "R10") (pin "1") (pinfunction "1_1") (pintype "passive"))
      (node (ref "R9") (pin "2") (pinfunction "2_2") (pintype "passive"))
      (node (ref "U6") (pin "4") (pinfunction "-IN_4") (pintype "bidirectional"))
    )
    (net (code "55") (name "PLAYOUT") (class "Default")
      (node (ref "J8") (pin "2") (pinfunction "2_2") (pintype "passive"))
      (node (ref "U4") (pin "25") (pinfunction "PC5_25") (pintype "bidirectional"))
    )
    (net (code "56") (name "RXD") (class "Default")
      (node (ref "R14") (pin "1") (pinfunction "1_1") (pintype "passive"))
      (node (ref "R15") (pin "1") (pinfunction "1_1") (pintype "passive"))
      (node (ref "U4") (pin "43") (pinfunction "PA10/UART1_RX_43") (pintype "bidirectional"))
    )
    (net (code "57") (name "SD_CD") (class "Default")
      (node (ref "J3") (pin "CD1") (pinfunction "SHIELD_CD1") (pintype "bidirectional"))
      (node (ref "J3") (pin "CD2") (pinfunction "SHIELD_CD2") (pintype "bidirectional"))
      (node (ref "U4") (pin "26") (pinfunction "PB0_26") (pintype "bidirectional"))
    )
    (net (code "58") (name "SD_CK") (class "Default")
      (node (ref "J3") (pin "5") (pinfunction "SCK_5") (pintype "bidirectional"))
      (node (ref "U4") (pin "53") (pinfunction "PC12/SDIO_CLK_53") (pintype "bidirectional"))
    )
    (net (code "59") (name "SD_CMD") (class "Default")
      (node (ref "J3") (pin "3") (pinfunction "DI_3") (pintype "bidirectional"))
      (node (ref "R3") (pin "1") (pinfunction "1_1") (pintype "passive"))
      (node (ref "U4") (pin "54") (pinfunction "PD2/SDIO_CMD_54") (pintype "bidirectional"))
    )
    (net (code "60") (name "SD_D0") (class "Default")
      (node (ref "J3") (pin "7") (pinfunction "DO_7") (pintype "bidirectional"))
      (node (ref "R2") (pin "1") (pinfunction "1_1") (pintype "passive"))
      (node (ref "U4") (pin "39") (pinfunction "PC8/SDIO_D0_39") (pintype "bidirectional"))
    )
    (net (code "61") (name "SD_D1") (class "Default")
      (node (ref "J3") (pin "8") (pinfunction "RSV_8") (pintype "bidirectional"))
      (node (ref "R1") (pin "1") (pinfunction "1_1") (pintype "passive"))
      (node (ref "U4") (pin "40") (pinfunction "PC9/SDIO_D1_40") (pintype "bidirectional"))
    )
    (net (code "62") (name "SD_D2") (class "Default")
      (node (ref "J3") (pin "1") (pinfunction "NC_1") (pintype "bidirectional"))
      (node (ref "R5") (pin "1") (pinfunction "1_1") (pintype "passive"))
      (node (ref "U4") (pin "51") (pinfunction "PC10/SDIO_D2_51") (pintype "bidirectional"))
    )
    (net (code "63") (name "SD_D3") (class "Default")
      (node (ref "J3") (pin "2") (pinfunction "CS_2") (pintype "bidirectional"))
      (node (ref "R4") (pin "1") (pinfunction "1_1") (pintype "passive"))
      (node (ref "U4") (pin "52") (pinfunction "PC11/SDIO_D3_52") (pintype "bidirectional"))
    )
    (net (code "64") (name "SPKR+") (class "Default")
      (node (ref "J5") (pin "2") (pinfunction "2_2") (pintype "passive"))
      (node (ref "U6") (pin "8") (pinfunction "VO2_8") (pintype "bidirectional"))
    )
    (net (code "65") (name "SPKR-") (class "Default")
      (node (ref "J5") (pin "1") (pinfunction "1_1") (pintype "passive"))
      (node (ref "R10") (pin "2") (pinfunction "2_2") (pintype "passive"))
      (node (ref "U6") (pin "5") (pinfunction "VO1_5") (pintype "bidirectional"))
    )
    (net (code "66") (name "TRIG00") (class "Default")
      (node (ref "R40") (pin "2") (pinfunction "2_2") (pintype "passive"))
      (node (ref "U4") (pin "14") (pinfunction "PA0_14") (pintype "bidirectional"))
    )
    (net (code "67") (name "TRIG01") (class "Default")
      (node (ref "R39") (pin "2") (pinfunction "2_2") (pintype "passive"))
      (node (ref "U4") (pin "15") (pinfunction "PA1_15") (pintype "bidirectional"))
    )
    (net (code "68") (name "TRIG02") (class "Default")
      (node (ref "R38") (pin "2") (pinfunction "2_2") (pintype "passive"))
      (node (ref "U4") (pin "16") (pinfunction "PA2/UART2_TX_16") (pintype "bidirectional"))
    )
    (net (code "69") (name "TRIG03") (class "Default")
      (node (ref "R37") (pin "2") (pinfunction "2_2") (pintype "passive"))
      (node (ref "U4") (pin "17") (pinfunction "PA3/UART2_RX_17") (pintype "bidirectional"))
    )
    (net (code "70") (name "TRIG04") (class "Default")
      (node (ref "R36") (pin "2") (pinfunction "2_2") (pintype "passive"))
      (node (ref "U4") (pin "20") (pinfunction "PA4/SPI1_NSS_20") (pintype "bidirectional"))
    )
    (net (code "71") (name "TRIG05") (class "Default")
      (node (ref "R35") (pin "2") (pinfunction "2_2") (pintype "passive"))
      (node (ref "U4") (pin "21") (pinfunction "PA5/SPI1_SCK_21") (pintype "bidirectional"))
    )
    (net (code "72") (name "TRIG06") (class "Default")
      (node (ref "R34") (pin "2") (pinfunction "2_2") (pintype "passive"))
      (node (ref "U4") (pin "22") (pinfunction "PA6/SPI1_MISO_22") (pintype "bidirectional"))
    )
    (net (code "73") (name "TRIG07") (class "Default")
      (node (ref "R33") (pin "2") (pinfunction "2_2") (pintype "passive"))
      (node (ref "U4") (pin "23") (pinfunction "PA7/SPI1_MOSI_23") (pintype "bidirectional"))
    )
    (net (code "74") (name "TRIG08") (class "Default")
      (node (ref "R11") (pin "2") (pinfunction "2_2") (pintype "passive"))
      (node (ref "U4") (pin "61") (pinfunction "PB8_61") (pintype "bidirectional"))
    )
    (net (code "75") (name "TRIG09") (class "Default")
      (node (ref "R12") (pin "2") (pinfunction "2_2") (pintype "passive"))
      (node (ref "U4") (pin "62") (pinfunction "PB9_62") (pintype "bidirectional"))
    )
    (net (code "76") (name "TRIG10") (class "Default")
      (node (ref "R13") (pin "2") (pinfunction "2_2") (pintype "passive"))
      (node (ref "U4") (pin "29") (pinfunction "PB10_29") (pintype "bidirectional"))
    )
    (net (code "77") (name "TRIG11") (class "Default")
      (node (ref "R18") (pin "2") (pinfunction "2_2") (pintype "passive"))
      (node (ref "U4") (pin "44") (pinfunction "PA11_44") (pintype "bidirectional"))
    )
    (net (code "78") (name "TRIG12") (class "Default")
      (node (ref "R21") (pin "2") (pinfunction "2_2") (pintype "passive"))
      (node (ref "U4") (pin "45") (pinfunction "PA12_45") (pintype "bidirectional"))
    )
    (net (code "79") (name "TRIG13") (class "Default")
      (node (ref "R22") (pin "2") (pinfunction "2_2") (pintype "passive"))
      (node (ref "U4") (pin "46") (pinfunction "PA13/JTMS_46") (pintype "bidirectional"))
    )
    (net (code "80") (name "TRIG14") (class "Default")
      (node (ref "R23") (pin "2") (pinfunction "2_2") (pintype "passive"))
      (node (ref "U4") (pin "49") (pinfunction "PA14/JTCK_49") (pintype "bidirectional"))
    )
    (net (code "81") (name "TRIG15") (class "Default")
      (node (ref "R24") (pin "2") (pinfunction "2_2") (pintype "passive"))
      (node (ref "U4") (pin "50") (pinfunction "PA15/JTDI_50") (pintype "bidirectional"))
    )
    (net (code "82") (name "TXD") (class "Default")
      (node (ref "J4") (pin "5") (pinfunction "5_5") (pintype "passive"))
      (node (ref "U4") (pin "42") (pinfunction "PA9/UART1_TX_42") (pintype "bidirectional"))
    )
    (net (code "83") (name "VIN") (class "Default")
      (node (ref "C1") (pin "1") (pinfunction "1_1") (pintype "passive"))
      (node (ref "J1") (pin "VIN0") (pinfunction "PWR_VIN0") (pintype "bidirectional"))
      (node (ref "J9") (pin "2") (pinfunction "2_2") (pintype "passive"))
      (node (ref "U1") (pin "3") (pinfunction "IN_3") (pintype "input"))
    )
    (net (code "84") (name "unconnected-(J4-Pad2)") (class "Default")
      (node (ref "J4") (pin "2") (pinfunction "2_2") (pintype "passive"))
    )
    (net (code "85") (name "unconnected-(J4-Pad6)") (class "Default")
      (node (ref "J4") (pin "6") (pinfunction "6_6") (pintype "passive"))
    )
    (net (code "86") (name "unconnected-(U4-PA8-Pad41)") (class "Default")
      (node (ref "U4") (pin "41") (pinfunction "PA8_41") (pintype "bidirectional"))
    )
    (net (code "87") (name "unconnected-(U4-PB3{slash}JTDO-Pad55)") (class "Default")
      (node (ref "U4") (pin "55") (pinfunction "PB3/JTDO_55") (pintype "bidirectional"))
    )
    (net (code "88") (name "unconnected-(U4-PB4{slash}JTRST-Pad56)") (class "Default")
      (node (ref "U4") (pin "56") (pinfunction "PB4/JTRST_56") (pintype "bidirectional"))
    )
    (net (code "89") (name "unconnected-(U4-PB5-Pad57)") (class "Default")
      (node (ref "U4") (pin "57") (pinfunction "PB5_57") (pintype "bidirectional"))
    )
    (net (code "90") (name "unconnected-(U4-PB6-Pad58)") (class "Default")
      (node (ref "U4") (pin "58") (pinfunction "PB6_58") (pintype "bidirectional"))
    )
    (net (code "91") (name "unconnected-(U4-PB7-Pad59)") (class "Default")
      (node (ref "U4") (pin "59") (pinfunction "PB7_59") (pintype "bidirectional"))
    )
    (net (code "92") (name "unconnected-(U4-PB11-Pad30)") (class "Default")
      (node (ref "U4") (pin "30") (pinfunction "PB11_30") (pintype "bidirectional"))
    )
    (net (code "93") (name "unconnected-(U4-PB14{slash}I2S2_XD-Pad35)") (class "Default")
      (node (ref "U4") (pin "35") (pinfunction "PB14/I2S2_XD_35") (pintype "bidirectional"))
    )
    (net (code "94") (name "unconnected-(U4-PC7-Pad38)") (class "Default")
      (node (ref "U4") (pin "38") (pinfunction "PC7_38") (pintype "bidirectional"))
    )
    (net (code "95") (name "unconnected-(U4-PC13-Pad2)") (class "Default")
      (node (ref "U4") (pin "2") (pinfunction "PC13_2") (pintype "bidirectional"))
    )
    (net (code "96") (name "unconnected-(U4-PC14-Pad3)") (class "Default")
      (node (ref "U4") (pin "3") (pinfunction "PC14_3") (pintype "bidirectional"))
    )
    (net (code "97") (name "unconnected-(U4-PC15-Pad4)") (class "Default")
      (node (ref "U4") (pin "4") (pinfunction "PC15_4") (pintype "bidirectional"))
    )
  )
)
